# EEPROM.net
KiCad netlist of a schematic drawn in Altium Designer
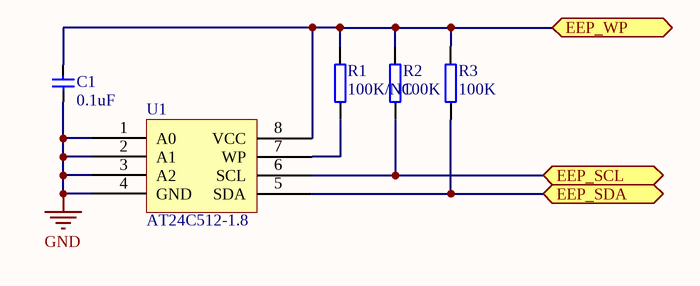
[diagram p0: EEPROM.SchDoc]

(export (version "E")
  (design (tool "Eeschema 10.0.6"))
  (components
    (comp (ref "C1") (value "0.1uF") (footprint "0603C") (libsource (lib "dtu02") (part "CAP")))
    (comp (ref "R1") (value "100K/NC") (footprint "0603R") (libsource (lib "dtu02") (part "RES2A")))
    (comp (ref "R2") (value "100K") (footprint "0603R") (libsource (lib "dtu02") (part "RES2A")))
    (comp (ref "R3") (value "100K") (footprint "0603R") (libsource (lib "dtu02") (part "RES2A")))
    (comp (ref "U1")
      (value "AT24C512-1.8")
      (footprint "SOP8")
      (libsource (lib "Schlib1") (part "AT24C512-1.8"))
    )
  )
  (nets
    (net (code "1") (name "/EEP_SCL") (class "Default")
      (node (ref "R2") (pin "2") (pintype "passive"))
      (node (ref "U1") (pin "6") (pinfunction "SCL_6") (pintype "passive"))
    )
    (net (code "2") (name "/EEP_SDA") (class "Default")
      (node (ref "R3") (pin "2") (pintype "passive"))
      (node (ref "U1") (pin "5") (pinfunction "SDA_5") (pintype "passive"))
    )
    (net (code "3") (name "/EEP_WP") (class "Default")
      (node (ref "C1") (pin "2") (pintype "passive"))
      (node (ref "R1") (pin "2") (pintype "passive"))
      (node (ref "R2") (pin "1") (pintype "passive"))
      (node (ref "R3") (pin "1") (pintype "passive"))
      (node (ref "U1") (pin "8") (pinfunction "VCC_8") (pintype "passive"))
    )
    (net (code "4") (name "GND") (class "Default")
      (node (ref "C1") (pin "1") (pintype "passive"))
      (node (ref "U1") (pin "1") (pinfunction "A0_1") (pintype "passive"))
      (node (ref "U1") (pin "2") (pinfunction "A1_2") (pintype "passive"))
      (node (ref "U1") (pin "3") (pinfunction "A2_3") (pintype "passive"))
      (node (ref "U1") (pin "4") (pinfunction "GND_4") (pintype "passive"))
    )
    (net (code "5") (name "Net-(U1-WP)") (class "Default")
      (node (ref "R1") (pin "1") (pintype "passive"))
      (node (ref "U1") (pin "7") (pinfunction "WP_7") (pintype "passive"))
    )
  )
)
